# shield-shield.net
KiCad netlist of a schematic drawn in EAGLE
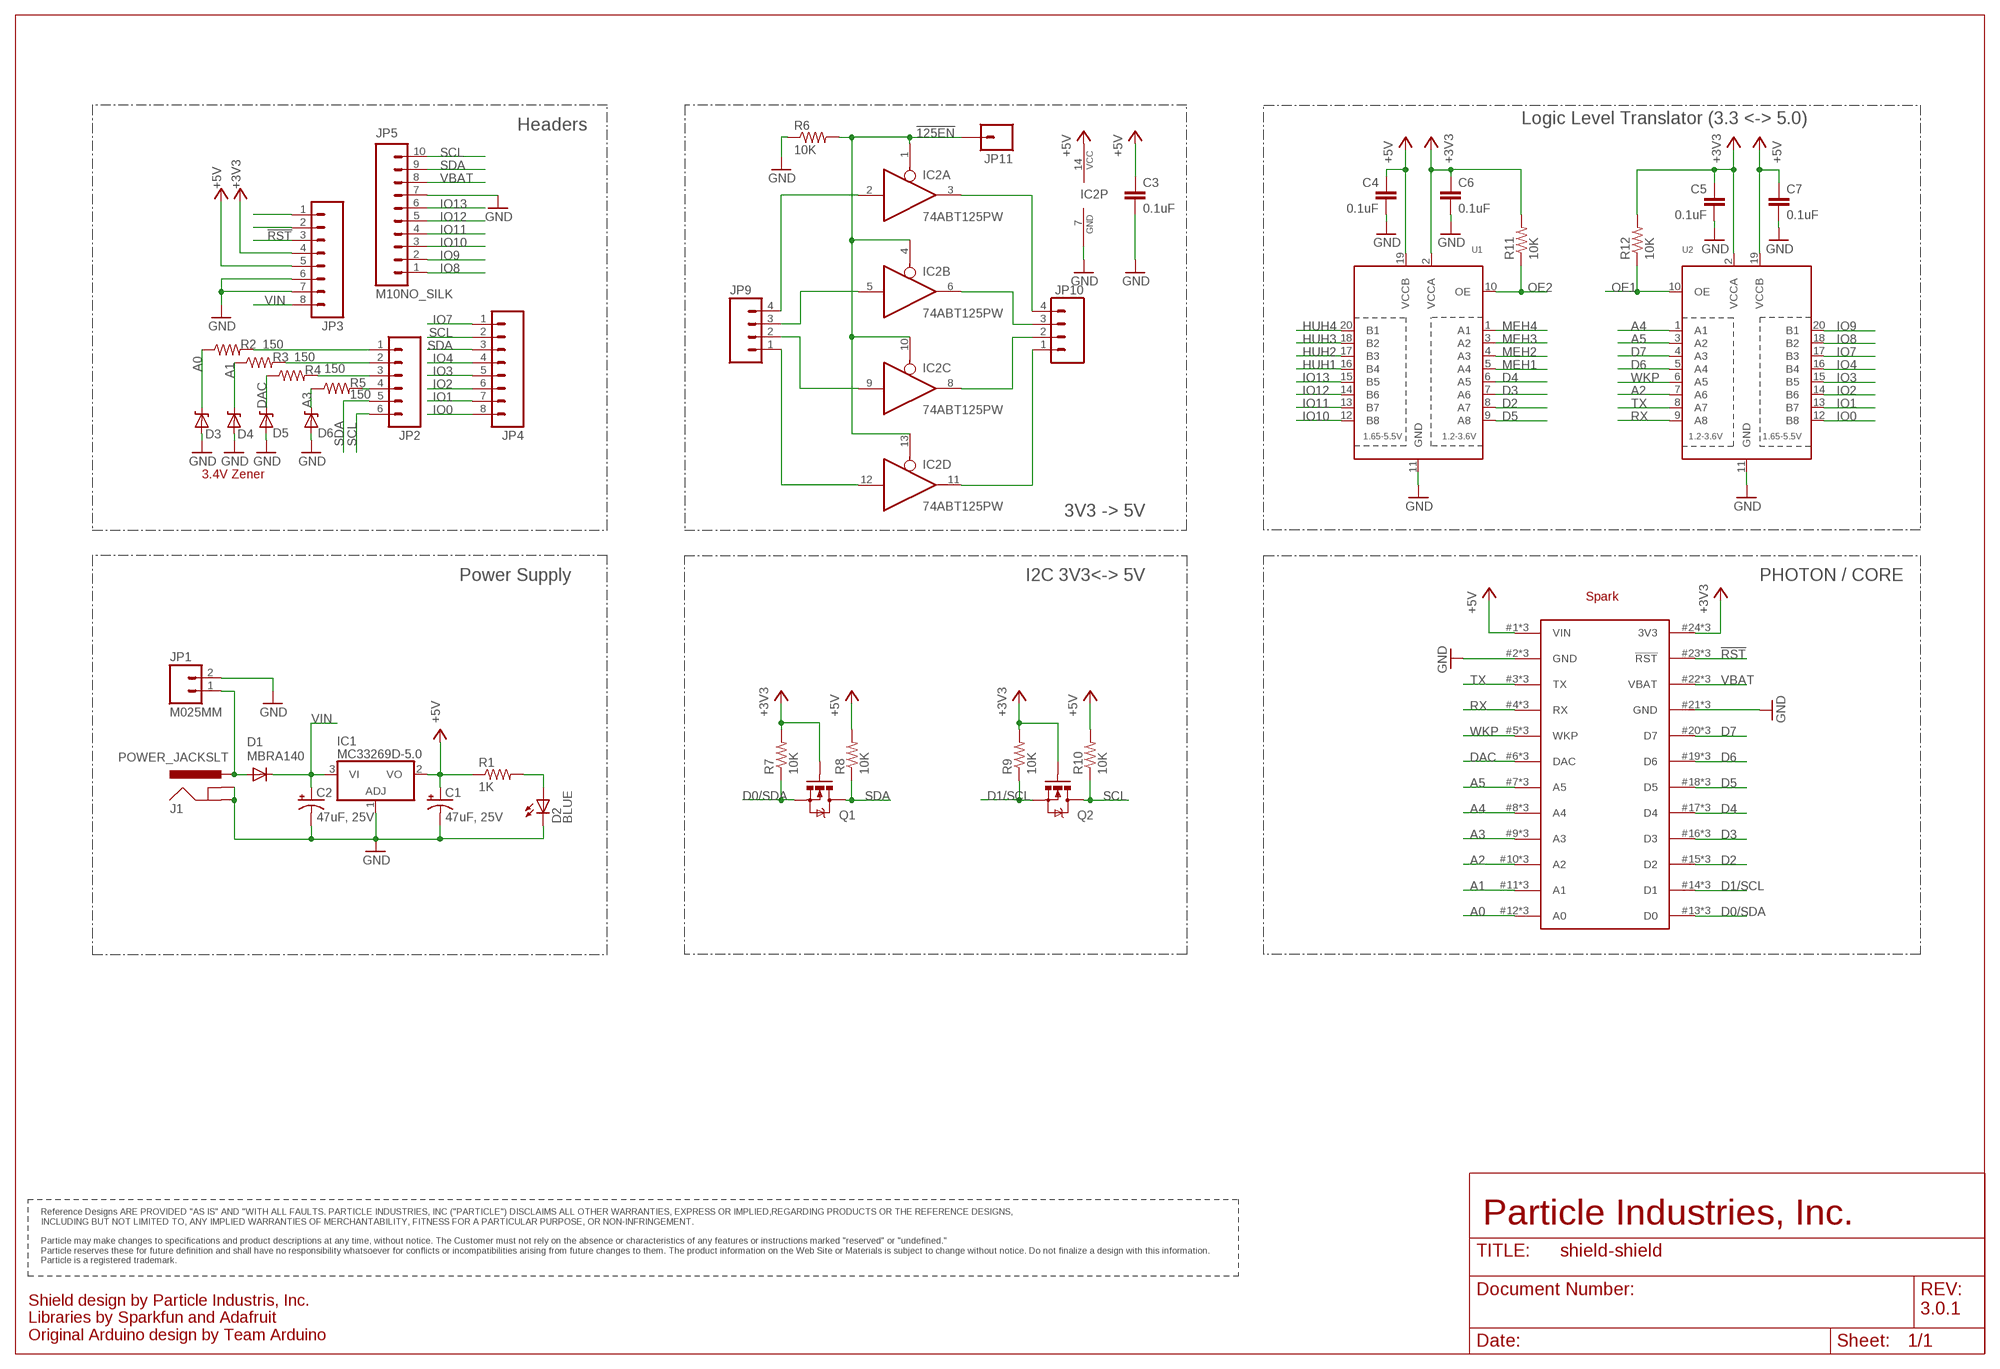
[diagram p0: schematic, sheet 1]

(export (version "E")
  (design (tool "Eeschema 10.0.6"))
  (components
    (comp (ref "C1")
      (value "47uF, 25V")
      (footprint "eagle-import:PANASONIC_D")
      (libsource (lib "eagle-import") (part "CAP_POLD"))
    )
    (comp (ref "C2")
      (value "47uF, 25V")
      (footprint "eagle-import:PANASONIC_D")
      (libsource (lib "eagle-import") (part "CAP_POLD"))
    )
    (comp (ref "C3")
      (value "0.1uF")
      (footprint "eagle-import:0603-CAP")
      (libsource (lib "eagle-import") (part "0.1UF-25V(+80/-20%)(0603)"))
    )
    (comp (ref "C4")
      (value "0.1uF")
      (footprint "eagle-import:0603-CAP")
      (libsource (lib "eagle-import") (part "0.1UF-25V(+80/-20%)(0603)"))
    )
    (comp (ref "C5")
      (value "0.1uF")
      (footprint "eagle-import:0603-CAP")
      (libsource (lib "eagle-import") (part "0.1UF-25V(+80/-20%)(0603)"))
    )
    (comp (ref "C6")
      (value "0.1uF")
      (footprint "eagle-import:0603-CAP")
      (libsource (lib "eagle-import") (part "0.1UF-25V(+80/-20%)(0603)"))
    )
    (comp (ref "C7")
      (value "0.1uF")
      (footprint "eagle-import:0603-CAP")
      (libsource (lib "eagle-import") (part "0.1UF-25V(+80/-20%)(0603)"))
    )
    (comp (ref "D1")
      (value "MBRA140")
      (footprint "eagle-import:SMA-DIODE")
      (libsource (lib "eagle-import") (part "DIODESMA"))
    )
    (comp (ref "D2")
      (value "BLUE")
      (footprint "eagle-import:LED-0603")
      (libsource (lib "eagle-import") (part "LED-BLUE0603"))
    )
    (comp (ref "D3")
      (value "DIODE-ZENER-BZT52")
      (footprint "eagle-import:SOD-323")
      (libsource (lib "eagle-import") (part "DIODE-ZENER-BZT52"))
    )
    (comp (ref "D4")
      (value "DIODE-ZENER-BZT52")
      (footprint "eagle-import:SOD-323")
      (libsource (lib "eagle-import") (part "DIODE-ZENER-BZT52"))
    )
    (comp (ref "D5")
      (value "DIODE-ZENER-BZT52")
      (footprint "eagle-import:SOD-323")
      (libsource (lib "eagle-import") (part "DIODE-ZENER-BZT52"))
    )
    (comp (ref "D6")
      (value "DIODE-ZENER-BZT52")
      (footprint "eagle-import:SOD-323")
      (libsource (lib "eagle-import") (part "DIODE-ZENER-BZT52"))
    )
    (comp (ref "IC1")
      (value "MC33269D-5.0")
      (footprint "eagle-import:DPACK")
      (libsource (lib "eagle-import") (part "MC33269?D-5.0"))
    )
    (comp (ref "IC2")
      (value "74ABT125PW")
      (footprint "eagle-import:TSSOP14")
      (libsource (lib "eagle-import") (part "74125PWABT"))
    )
    (comp (ref "J1")
      (value "POWER_JACKSLT")
      (footprint "eagle-import:POWER_JACK_SLOT")
      (libsource (lib "eagle-import") (part "POWER_JACKSLT"))
    )
    (comp (ref "JP1")
      (value "M025MM")
      (footprint "eagle-import:SCREWTERMINAL-5MM-2")
      (libsource (lib "eagle-import") (part "M025MM"))
    )
    (comp (ref "JP2")
      (value "M06NO_SILK")
      (footprint "eagle-import:1X06_NO_SILK")
      (libsource (lib "eagle-import") (part "M06NO_SILK"))
    )
    (comp (ref "JP3")
      (value "M08NO_SILK")
      (footprint "eagle-import:1X08_NO_SILK")
      (libsource (lib "eagle-import") (part "M08NO_SILK"))
    )
    (comp (ref "JP4")
      (value "M08NO_SILK")
      (footprint "eagle-import:1X08_NO_SILK")
      (libsource (lib "eagle-import") (part "M08NO_SILK"))
    )
    (comp (ref "JP5")
      (value "M10NO_SILK")
      (footprint "eagle-import:1X10_NO_SILK")
      (libsource (lib "eagle-import") (part "M10NO_SILK"))
    )
    (comp (ref "JP9")
      (value "M041X04_NO_SILK")
      (footprint "eagle-import:1X04_NO_SILK")
      (libsource (lib "eagle-import") (part "M041X04_NO_SILK"))
    )
    (comp (ref "JP10")
      (value "M041X04_NO_SILK")
      (footprint "eagle-import:1X04_NO_SILK")
      (libsource (lib "eagle-import") (part "M041X04_NO_SILK"))
    )
    (comp (ref "JP11")
      (value "M01NOSILK-KIT")
      (footprint "eagle-import:1X01NS-KIT")
      (libsource (lib "eagle-import") (part "M01NOSILK-KIT"))
    )
    (comp (ref "Q1")
      (value "MOSFET-NCHANNELBSS138")
      (footprint "eagle-import:SOT23")
      (libsource (lib "eagle-import") (part "MOSFET-NCHANNELBSS138"))
    )
    (comp (ref "Q2")
      (value "MOSFET-NCHANNELBSS138")
      (footprint "eagle-import:SOT23")
      (libsource (lib "eagle-import") (part "MOSFET-NCHANNELBSS138"))
    )
    (comp (ref "R1")
      (value "1K")
      (footprint "eagle-import:0603-RES")
      (libsource (lib "eagle-import") (part "RESISTOR0603-RES"))
    )
    (comp (ref "R2")
      (value "150")
      (footprint "eagle-import:0603-RES")
      (libsource (lib "eagle-import") (part "RESISTOR0603-RES"))
    )
    (comp (ref "R3")
      (value "150")
      (footprint "eagle-import:0603-RES")
      (libsource (lib "eagle-import") (part "RESISTOR0603-RES"))
    )
    (comp (ref "R4")
      (value "150")
      (footprint "eagle-import:0603-RES")
      (libsource (lib "eagle-import") (part "RESISTOR0603-RES"))
    )
    (comp (ref "R5")
      (value "150")
      (footprint "eagle-import:0603-RES")
      (libsource (lib "eagle-import") (part "RESISTOR0603-RES"))
    )
    (comp (ref "R6")
      (value "10K")
      (footprint "eagle-import:0603-RES")
      (libsource (lib "eagle-import") (part "RESISTOR0603-RES"))
    )
    (comp (ref "R7")
      (value "10K")
      (footprint "eagle-import:0603-RES")
      (libsource (lib "eagle-import") (part "RESISTOR0603-RES"))
    )
    (comp (ref "R8")
      (value "10K")
      (footprint "eagle-import:0603-RES")
      (libsource (lib "eagle-import") (part "RESISTOR0603-RES"))
    )
    (comp (ref "R9")
      (value "10K")
      (footprint "eagle-import:0603-RES")
      (libsource (lib "eagle-import") (part "RESISTOR0603-RES"))
    )
    (comp (ref "R10")
      (value "10K")
      (footprint "eagle-import:0603-RES")
      (libsource (lib "eagle-import") (part "RESISTOR0603-RES"))
    )
    (comp (ref "R11")
      (value "10K")
      (footprint "eagle-import:0603-RES")
      (libsource (lib "eagle-import") (part "RESISTOR0603-RES"))
    )
    (comp (ref "R12")
      (value "10K")
      (footprint "eagle-import:0603-RES")
      (libsource (lib "eagle-import") (part "RESISTOR0603-RES"))
    )
    (comp (ref "U$1")
      (value "SPARK_CORE")
      (footprint "eagle-import:SPARK_CORE_STACKABLE")
      (libsource (lib "eagle-import") (part "SPARK_CORESTACKABLE"))
    )
    (comp (ref "U$2")
      (value "SPARK_LOGO")
      (footprint "eagle-import:SPARK_LOGO_TSTOP")
      (libsource (lib "eagle-import") (part "SPARK_LOGO"))
    )
    (comp (ref "U1")
      (value "TXB0108PWR")
      (footprint "eagle-import:TSSOP20")
      (libsource (lib "eagle-import") (part "TXB0108PWR"))
    )
    (comp (ref "U2")
      (value "TXB0108PWR")
      (footprint "eagle-import:TSSOP20")
      (libsource (lib "eagle-import") (part "TXB0108PWR"))
    )
  )
  (nets
    (net (code "1") (name "+3V3") (class "Default")
      (node (ref "C5") (pin "1") (pinfunction "1_1") (pintype "passive"))
      (node (ref "C6") (pin "1") (pinfunction "1_1") (pintype "passive"))
      (node (ref "JP3") (pin "4") (pinfunction "4_4") (pintype "passive"))
      (node (ref "Q1") (pin "1") (pinfunction "G_1") (pintype "passive"))
      (node (ref "Q2") (pin "1") (pinfunction "G_1") (pintype "passive"))
      (node (ref "R11") (pin "2") (pinfunction "2_2") (pintype "passive"))
      (node (ref "R12") (pin "2") (pinfunction "2_2") (pintype "passive"))
      (node (ref "R7") (pin "2") (pinfunction "2_2") (pintype "passive"))
      (node (ref "R9") (pin "2") (pinfunction "2_2") (pintype "passive"))
      (node (ref "U$1") (pin "#24") (pinfunction "3V3_#24") (pintype "power_in"))
      (node (ref "U$1") (pin "24") (pinfunction "3V3_24") (pintype "power_in"))
      (node (ref "U$1") (pin "@24") (pinfunction "3V3_@24") (pintype "power_in"))
      (node (ref "U1") (pin "2") (pinfunction "VCCA_2") (pintype "bidirectional"))
      (node (ref "U2") (pin "2") (pinfunction "VCCA_2") (pintype "bidirectional"))
    )
    (net (code "2") (name "+5V") (class "Default")
      (node (ref "C1") (pin "+") (pinfunction "+_+") (pintype "passive"))
      (node (ref "C3") (pin "1") (pinfunction "1_1") (pintype "passive"))
      (node (ref "C4") (pin "1") (pinfunction "1_1") (pintype "passive"))
      (node (ref "C7") (pin "1") (pinfunction "1_1") (pintype "passive"))
      (node (ref "IC1") (pin "2") (pinfunction "VO_2") (pintype "passive"))
      (node (ref "IC2") (pin "14") (pinfunction "VCC_14") (pintype "power_in"))
      (node (ref "JP3") (pin "5") (pinfunction "5_5") (pintype "passive"))
      (node (ref "R1") (pin "1") (pinfunction "1_1") (pintype "passive"))
      (node (ref "R10") (pin "2") (pinfunction "2_2") (pintype "passive"))
      (node (ref "R8") (pin "2") (pinfunction "2_2") (pintype "passive"))
      (node (ref "U$1") (pin "#1") (pinfunction "VIN_#1") (pintype "power_in"))
      (node (ref "U$1") (pin "1") (pinfunction "VIN_1") (pintype "power_in"))
      (node (ref "U$1") (pin "@1") (pinfunction "VIN_@1") (pintype "power_in"))
      (node (ref "U1") (pin "19") (pinfunction "VCCB_19") (pintype "bidirectional"))
      (node (ref "U2") (pin "19") (pinfunction "VCCB_19") (pintype "bidirectional"))
    )
    (net (code "3") (name "/A0") (class "Default")
      (node (ref "D3") (pin "1") (pinfunction "C_1") (pintype "passive"))
      (node (ref "R2") (pin "1") (pinfunction "1_1") (pintype "passive"))
      (node (ref "U$1") (pin "#12") (pinfunction "A0_#12") (pintype "bidirectional"))
      (node (ref "U$1") (pin "12") (pinfunction "A0_12") (pintype "bidirectional"))
      (node (ref "U$1") (pin "@12") (pinfunction "A0_@12") (pintype "bidirectional"))
    )
    (net (code "4") (name "/A1") (class "Default")
      (node (ref "D4") (pin "1") (pinfunction "C_1") (pintype "passive"))
      (node (ref "R3") (pin "1") (pinfunction "1_1") (pintype "passive"))
      (node (ref "U$1") (pin "#11") (pinfunction "A1_#11") (pintype "bidirectional"))
      (node (ref "U$1") (pin "11") (pinfunction "A1_11") (pintype "bidirectional"))
      (node (ref "U$1") (pin "@11") (pinfunction "A1_@11") (pintype "bidirectional"))
    )
    (net (code "5") (name "/A2") (class "Default")
      (node (ref "U$1") (pin "#10") (pinfunction "A2_#10") (pintype "bidirectional"))
      (node (ref "U$1") (pin "10") (pinfunction "A2_10") (pintype "bidirectional"))
      (node (ref "U$1") (pin "@10") (pinfunction "A2_@10") (pintype "bidirectional"))
      (node (ref "U2") (pin "7") (pinfunction "A6_7") (pintype "bidirectional"))
    )
    (net (code "6") (name "/A3") (class "Default")
      (node (ref "D6") (pin "1") (pinfunction "C_1") (pintype "passive"))
      (node (ref "R5") (pin "1") (pinfunction "1_1") (pintype "passive"))
      (node (ref "U$1") (pin "#9") (pinfunction "A3_#9") (pintype "bidirectional"))
      (node (ref "U$1") (pin "9") (pinfunction "A3_9") (pintype "bidirectional"))
      (node (ref "U$1") (pin "@9") (pinfunction "A3_@9") (pintype "bidirectional"))
    )
    (net (code "7") (name "/A4") (class "Default")
      (node (ref "U$1") (pin "#8") (pinfunction "A4_#8") (pintype "bidirectional"))
      (node (ref "U$1") (pin "8") (pinfunction "A4_8") (pintype "bidirectional"))
      (node (ref "U$1") (pin "@8") (pinfunction "A4_@8") (pintype "bidirectional"))
      (node (ref "U2") (pin "1") (pinfunction "A1_1") (pintype "bidirectional"))
    )
    (net (code "8") (name "/A5") (class "Default")
      (node (ref "U$1") (pin "#7") (pinfunction "A5_#7") (pintype "bidirectional"))
      (node (ref "U$1") (pin "7") (pinfunction "A5_7") (pintype "bidirectional"))
      (node (ref "U$1") (pin "@7") (pinfunction "A5_@7") (pintype "bidirectional"))
      (node (ref "U2") (pin "3") (pinfunction "A2_3") (pintype "bidirectional"))
    )
    (net (code "9") (name "/D0{slash}SDA") (class "Default")
      (node (ref "Q1") (pin "2") (pinfunction "S_2") (pintype "passive"))
      (node (ref "R7") (pin "1") (pinfunction "1_1") (pintype "passive"))
      (node (ref "U$1") (pin "#13") (pinfunction "D0_#13") (pintype "bidirectional"))
      (node (ref "U$1") (pin "13") (pinfunction "D0_13") (pintype "bidirectional"))
      (node (ref "U$1") (pin "@13") (pinfunction "D0_@13") (pintype "bidirectional"))
    )
    (net (code "10") (name "/D1{slash}SCL") (class "Default")
      (node (ref "Q2") (pin "2") (pinfunction "S_2") (pintype "passive"))
      (node (ref "R9") (pin "1") (pinfunction "1_1") (pintype "passive"))
      (node (ref "U$1") (pin "#14") (pinfunction "D1_#14") (pintype "bidirectional"))
      (node (ref "U$1") (pin "14") (pinfunction "D1_14") (pintype "bidirectional"))
      (node (ref "U$1") (pin "@14") (pinfunction "D1_@14") (pintype "bidirectional"))
    )
    (net (code "11") (name "/D2") (class "Default")
      (node (ref "U$1") (pin "#15") (pinfunction "D2_#15") (pintype "bidirectional"))
      (node (ref "U$1") (pin "15") (pinfunction "D2_15") (pintype "bidirectional"))
      (node (ref "U$1") (pin "@15") (pinfunction "D2_@15") (pintype "bidirectional"))
      (node (ref "U1") (pin "8") (pinfunction "A7_8") (pintype "bidirectional"))
    )
    (net (code "12") (name "/D3") (class "Default")
      (node (ref "U$1") (pin "#16") (pinfunction "D3_#16") (pintype "bidirectional"))
      (node (ref "U$1") (pin "16") (pinfunction "D3_16") (pintype "bidirectional"))
      (node (ref "U$1") (pin "@16") (pinfunction "D3_@16") (pintype "bidirectional"))
      (node (ref "U1") (pin "7") (pinfunction "A6_7") (pintype "bidirectional"))
    )
    (net (code "13") (name "/D4") (class "Default")
      (node (ref "U$1") (pin "#17") (pinfunction "D4_#17") (pintype "bidirectional"))
      (node (ref "U$1") (pin "17") (pinfunction "D4_17") (pintype "bidirectional"))
      (node (ref "U$1") (pin "@17") (pinfunction "D4_@17") (pintype "bidirectional"))
      (node (ref "U1") (pin "6") (pinfunction "A5_6") (pintype "bidirectional"))
    )
    (net (code "14") (name "/D5") (class "Default")
      (node (ref "U$1") (pin "#18") (pinfunction "D5_#18") (pintype "bidirectional"))
      (node (ref "U$1") (pin "18") (pinfunction "D5_18") (pintype "bidirectional"))
      (node (ref "U$1") (pin "@18") (pinfunction "D5_@18") (pintype "bidirectional"))
      (node (ref "U1") (pin "9") (pinfunction "A8_9") (pintype "bidirectional"))
    )
    (net (code "15") (name "/D6") (class "Default")
      (node (ref "U$1") (pin "#19") (pinfunction "D6_#19") (pintype "bidirectional"))
      (node (ref "U$1") (pin "19") (pinfunction "D6_19") (pintype "bidirectional"))
      (node (ref "U$1") (pin "@19") (pinfunction "D6_@19") (pintype "bidirectional"))
      (node (ref "U2") (pin "5") (pinfunction "A4_5") (pintype "bidirectional"))
    )
    (net (code "16") (name "/D7") (class "Default")
      (node (ref "U$1") (pin "#20") (pinfunction "D7_#20") (pintype "bidirectional"))
      (node (ref "U$1") (pin "20") (pinfunction "D7_20") (pintype "bidirectional"))
      (node (ref "U$1") (pin "@20") (pinfunction "D7_@20") (pintype "bidirectional"))
      (node (ref "U2") (pin "4") (pinfunction "A3_4") (pintype "bidirectional"))
    )
    (net (code "17") (name "/DAC") (class "Default")
      (node (ref "D5") (pin "1") (pinfunction "C_1") (pintype "passive"))
      (node (ref "R4") (pin "1") (pinfunction "1_1") (pintype "passive"))
      (node (ref "U$1") (pin "#6") (pinfunction "DAC_#6") (pintype "bidirectional"))
      (node (ref "U$1") (pin "6") (pinfunction "DAC_6") (pintype "bidirectional"))
      (node (ref "U$1") (pin "@6") (pinfunction "DAC_@6") (pintype "bidirectional"))
    )
    (net (code "18") (name "/HUH1") (class "Default")
      (node (ref "U1") (pin "16") (pinfunction "B4_16") (pintype "bidirectional"))
    )
    (net (code "19") (name "/HUH2") (class "Default")
      (node (ref "U1") (pin "17") (pinfunction "B3_17") (pintype "bidirectional"))
    )
    (net (code "20") (name "/HUH3") (class "Default")
      (node (ref "U1") (pin "18") (pinfunction "B2_18") (pintype "bidirectional"))
    )
    (net (code "21") (name "/HUH4") (class "Default")
      (node (ref "U1") (pin "20") (pinfunction "B1_20") (pintype "bidirectional"))
    )
    (net (code "22") (name "/IO0") (class "Default")
      (node (ref "JP4") (pin "8") (pinfunction "8_8") (pintype "passive"))
      (node (ref "U2") (pin "12") (pinfunction "B8_12") (pintype "bidirectional"))
    )
    (net (code "23") (name "/IO1") (class "Default")
      (node (ref "JP4") (pin "7") (pinfunction "7_7") (pintype "passive"))
      (node (ref "U2") (pin "13") (pinfunction "B7_13") (pintype "bidirectional"))
    )
    (net (code "24") (name "/IO2") (class "Default")
      (node (ref "JP4") (pin "6") (pinfunction "6_6") (pintype "passive"))
      (node (ref "U2") (pin "14") (pinfunction "B6_14") (pintype "bidirectional"))
    )
    (net (code "25") (name "/IO3") (class "Default")
      (node (ref "JP4") (pin "5") (pinfunction "5_5") (pintype "passive"))
      (node (ref "U2") (pin "15") (pinfunction "B5_15") (pintype "bidirectional"))
    )
    (net (code "26") (name "/IO4") (class "Default")
      (node (ref "JP4") (pin "4") (pinfunction "4_4") (pintype "passive"))
      (node (ref "U2") (pin "16") (pinfunction "B4_16") (pintype "bidirectional"))
    )
    (net (code "27") (name "/IO7") (class "Default")
      (node (ref "JP4") (pin "1") (pinfunction "1_1") (pintype "passive"))
      (node (ref "U2") (pin "17") (pinfunction "B3_17") (pintype "bidirectional"))
    )
    (net (code "28") (name "/IO8") (class "Default")
      (node (ref "JP5") (pin "1") (pinfunction "1_1") (pintype "passive"))
      (node (ref "U2") (pin "18") (pinfunction "B2_18") (pintype "bidirectional"))
    )
    (net (code "29") (name "/IO9") (class "Default")
      (node (ref "JP5") (pin "2") (pinfunction "2_2") (pintype "passive"))
      (node (ref "U2") (pin "20") (pinfunction "B1_20") (pintype "bidirectional"))
    )
    (net (code "30") (name "/IO10") (class "Default")
      (node (ref "JP5") (pin "3") (pinfunction "3_3") (pintype "passive"))
      (node (ref "U1") (pin "12") (pinfunction "B8_12") (pintype "bidirectional"))
    )
    (net (code "31") (name "/IO11") (class "Default")
      (node (ref "JP5") (pin "4") (pinfunction "4_4") (pintype "passive"))
      (node (ref "U1") (pin "13") (pinfunction "B7_13") (pintype "bidirectional"))
    )
    (net (code "32") (name "/IO12") (class "Default")
      (node (ref "JP5") (pin "5") (pinfunction "5_5") (pintype "passive"))
      (node (ref "U1") (pin "14") (pinfunction "B6_14") (pintype "bidirectional"))
    )
    (net (code "33") (name "/IO13") (class "Default")
      (node (ref "JP5") (pin "6") (pinfunction "6_6") (pintype "passive"))
      (node (ref "U1") (pin "15") (pinfunction "B5_15") (pintype "bidirectional"))
    )
    (net (code "34") (name "/MEH1") (class "Default")
      (node (ref "U1") (pin "5") (pinfunction "A4_5") (pintype "bidirectional"))
    )
    (net (code "35") (name "/MEH2") (class "Default")
      (node (ref "U1") (pin "4") (pinfunction "A3_4") (pintype "bidirectional"))
    )
    (net (code "36") (name "/MEH3") (class "Default")
      (node (ref "U1") (pin "3") (pinfunction "A2_3") (pintype "bidirectional"))
    )
    (net (code "37") (name "/MEH4") (class "Default")
      (node (ref "U1") (pin "1") (pinfunction "A1_1") (pintype "bidirectional"))
    )
    (net (code "38") (name "/OE1") (class "Default")
      (node (ref "R12") (pin "1") (pinfunction "1_1") (pintype "passive"))
      (node (ref "U2") (pin "10") (pinfunction "OE_10") (pintype "bidirectional"))
    )
    (net (code "39") (name "/OE2") (class "Default")
      (node (ref "R11") (pin "1") (pinfunction "1_1") (pintype "passive"))
      (node (ref "U1") (pin "10") (pinfunction "OE_10") (pintype "bidirectional"))
    )
    (net (code "40") (name "/RX") (class "Default")
      (node (ref "U$1") (pin "#4") (pinfunction "RX_#4") (pintype "bidirectional"))
      (node (ref "U$1") (pin "4") (pinfunction "RX_4") (pintype "bidirectional"))
      (node (ref "U$1") (pin "@4") (pinfunction "RX_@4") (pintype "bidirectional"))
      (node (ref "U2") (pin "9") (pinfunction "A8_9") (pintype "bidirectional"))
    )
    (net (code "41") (name "/SCL") (class "Default")
      (node (ref "JP2") (pin "6") (pinfunction "6_6") (pintype "passive"))
      (node (ref "JP4") (pin "2") (pinfunction "2_2") (pintype "passive"))
      (node (ref "JP5") (pin "10") (pinfunction "10_10") (pintype "passive"))
      (node (ref "Q2") (pin "3") (pinfunction "D_3") (pintype "passive"))
      (node (ref "R10") (pin "1") (pinfunction "1_1") (pintype "passive"))
    )
    (net (code "42") (name "/SDA") (class "Default")
      (node (ref "JP2") (pin "5") (pinfunction "5_5") (pintype "passive"))
      (node (ref "JP4") (pin "3") (pinfunction "3_3") (pintype "passive"))
      (node (ref "JP5") (pin "9") (pinfunction "9_9") (pintype "passive"))
      (node (ref "Q1") (pin "3") (pinfunction "D_3") (pintype "passive"))
      (node (ref "R8") (pin "1") (pinfunction "1_1") (pintype "passive"))
    )
    (net (code "43") (name "/TX") (class "Default")
      (node (ref "U$1") (pin "#3") (pinfunction "TX_#3") (pintype "bidirectional"))
      (node (ref "U$1") (pin "3") (pinfunction "TX_3") (pintype "bidirectional"))
      (node (ref "U$1") (pin "@3") (pinfunction "TX_@3") (pintype "bidirectional"))
      (node (ref "U2") (pin "8") (pinfunction "A7_8") (pintype "bidirectional"))
    )
    (net (code "44") (name "/VBAT") (class "Default")
      (node (ref "JP5") (pin "8") (pinfunction "8_8") (pintype "passive"))
      (node (ref "U$1") (pin "#22") (pinfunction "VBAT_#22") (pintype "power_in"))
      (node (ref "U$1") (pin "22") (pinfunction "VBAT_22") (pintype "power_in"))
      (node (ref "U$1") (pin "@22") (pinfunction "VBAT_@22") (pintype "power_in"))
    )
    (net (code "45") (name "/VIN") (class "Default")
      (node (ref "C2") (pin "+") (pinfunction "+_+") (pintype "passive"))
      (node (ref "D1") (pin "C") (pinfunction "C_C") (pintype "passive"))
      (node (ref "IC1") (pin "3") (pinfunction "VI_3") (pintype "input"))
      (node (ref "JP3") (pin "8") (pinfunction "8_8") (pintype "passive"))
    )
    (net (code "46") (name "/WKP") (class "Default")
      (node (ref "U$1") (pin "#5") (pinfunction "WKP_#5") (pintype "bidirectional"))
      (node (ref "U$1") (pin "5") (pinfunction "WKP_5") (pintype "bidirectional"))
      (node (ref "U$1") (pin "@5") (pinfunction "WKP_@5") (pintype "bidirectional"))
      (node (ref "U2") (pin "6") (pinfunction "A5_6") (pintype "bidirectional"))
    )
    (net (code "47") (name "/~{125EN}") (class "Default")
      (node (ref "IC2") (pin "1") (pinfunction "OE_1") (pintype "input"))
      (node (ref "IC2") (pin "10") (pinfunction "OE_10") (pintype "input"))
      (node (ref "IC2") (pin "13") (pinfunction "OE_13") (pintype "input"))
      (node (ref "IC2") (pin "4") (pinfunction "OE_4") (pintype "input"))
      (node (ref "JP11") (pin "1") (pinfunction "1_1") (pintype "passive"))
      (node (ref "R6") (pin "2") (pinfunction "2_2") (pintype "passive"))
    )
    (net (code "48") (name "/~{RST}") (class "Default")
      (node (ref "JP3") (pin "3") (pinfunction "3_3") (pintype "passive"))
      (node (ref "U$1") (pin "#23") (pinfunction "~{RST}_#23") (pintype "bidirectional"))
      (node (ref "U$1") (pin "23") (pinfunction "~{RST}_23") (pintype "bidirectional"))
      (node (ref "U$1") (pin "@23") (pinfunction "~{RST}_@23") (pintype "bidirectional"))
    )
    (net (code "49") (name "GND") (class "Default")
      (node (ref "C1") (pin "-") (pinfunction "-_-") (pintype "passive"))
      (node (ref "C2") (pin "-") (pinfunction "-_-") (pintype "passive"))
      (node (ref "C3") (pin "2") (pinfunction "2_2") (pintype "passive"))
      (node (ref "C4") (pin "2") (pinfunction "2_2") (pintype "passive"))
      (node (ref "C5") (pin "2") (pinfunction "2_2") (pintype "passive"))
      (node (ref "C6") (pin "2") (pinfunction "2_2") (pintype "passive"))
      (node (ref "C7") (pin "2") (pinfunction "2_2") (pintype "passive"))
      (node (ref "D2") (pin "C") (pinfunction "C_C") (pintype "passive"))
      (node (ref "D3") (pin "2") (pinfunction "A_2") (pintype "passive"))
      (node (ref "D4") (pin "2") (pinfunction "A_2") (pintype "passive"))
      (node (ref "D5") (pin "2") (pinfunction "A_2") (pintype "passive"))
      (node (ref "D6") (pin "2") (pinfunction "A_2") (pintype "passive"))
      (node (ref "IC1") (pin "1") (pinfunction "ADJ_1") (pintype "input"))
      (node (ref "IC2") (pin "7") (pinfunction "GND_7") (pintype "power_in"))
      (node (ref "J1") (pin "GND@1") (pinfunction "GNDBREAK_GND@1") (pintype "bidirectional"))
      (node (ref "J1") (pin "GND@2") (pinfunction "GND_GND@2") (pintype "bidirectional"))
      (node (ref "JP1") (pin "2") (pinfunction "2_2") (pintype "passive"))
      (node (ref "JP3") (pin "6") (pinfunction "6_6") (pintype "passive"))
      (node (ref "JP3") (pin "7") (pinfunction "7_7") (pintype "passive"))
      (node (ref "JP5") (pin "7") (pinfunction "7_7") (pintype "passive"))
      (node (ref "R6") (pin "1") (pinfunction "1_1") (pintype "passive"))
      (node (ref "U$1") (pin "#2") (pinfunction "GND_#2") (pintype "power_in"))
      (node (ref "U$1") (pin "#21") (pinfunction "GND_#21") (pintype "power_in"))
      (node (ref "U$1") (pin "2") (pinfunction "GND_2") (pintype "power_in"))
      (node (ref "U$1") (pin "21") (pinfunction "GND_21") (pintype "power_in"))
      (node (ref "U$1") (pin "@2") (pinfunction "GND_@2") (pintype "power_in"))
      (node (ref "U$1") (pin "@21") (pinfunction "GND_@21") (pintype "power_in"))
      (node (ref "U1") (pin "11") (pinfunction "GND_11") (pintype "bidirectional"))
      (node (ref "U2") (pin "11") (pinfunction "GND_11") (pintype "bidirectional"))
    )
    (net (code "50") (name "Net-(D1-PadA)") (class "Default")
      (node (ref "D1") (pin "A") (pinfunction "A_A") (pintype "passive"))
      (node (ref "J1") (pin "PWR") (pinfunction "PWR_PWR") (pintype "bidirectional"))
      (node (ref "JP1") (pin "1") (pinfunction "1_1") (pintype "passive"))
    )
    (net (code "51") (name "Net-(D2-PadA)") (class "Default")
      (node (ref "D2") (pin "A") (pinfunction "A_A") (pintype "passive"))
      (node (ref "R1") (pin "2") (pinfunction "2_2") (pintype "passive"))
    )
    (net (code "52") (name "Net-(IC2A-I)") (class "Default")
      (node (ref "IC2") (pin "2") (pinfunction "I_2") (pintype "input"))
      (node (ref "JP9") (pin "4") (pinfunction "4_4") (pintype "passive"))
    )
    (net (code "53") (name "Net-(IC2A-O)") (class "Default")
      (node (ref "IC2") (pin "3") (pinfunction "O_3") (pintype "tri_state"))
      (node (ref "JP10") (pin "4") (pinfunction "4_4") (pintype "passive"))
    )
    (net (code "54") (name "Net-(IC2B-I)") (class "Default")
      (node (ref "IC2") (pin "5") (pinfunction "I_5") (pintype "input"))
      (node (ref "JP9") (pin "3") (pinfunction "3_3") (pintype "passive"))
    )
    (net (code "55") (name "Net-(IC2B-O)") (class "Default")
      (node (ref "IC2") (pin "6") (pinfunction "O_6") (pintype "tri_state"))
      (node (ref "JP10") (pin "3") (pinfunction "3_3") (pintype "passive"))
    )
    (net (code "56") (name "Net-(IC2C-I)") (class "Default")
      (node (ref "IC2") (pin "9") (pinfunction "I_9") (pintype "input"))
      (node (ref "JP9") (pin "2") (pinfunction "2_2") (pintype "passive"))
    )
    (net (code "57") (name "Net-(IC2C-O)") (class "Default")
      (node (ref "IC2") (pin "8") (pinfunction "O_8") (pintype "tri_state"))
      (node (ref "JP10") (pin "2") (pinfunction "2_2") (pintype "passive"))
    )
    (net (code "58") (name "Net-(IC2D-I)") (class "Default")
      (node (ref "IC2") (pin "12") (pinfunction "I_12") (pintype "input"))
      (node (ref "JP9") (pin "1") (pinfunction "1_1") (pintype "passive"))
    )
    (net (code "59") (name "Net-(IC2D-O)") (class "Default")
      (node (ref "IC2") (pin "11") (pinfunction "O_11") (pintype "tri_state"))
      (node (ref "JP10") (pin "1") (pinfunction "1_1") (pintype "passive"))
    )
    (net (code "60") (name "Net-(JP2-Pad1)") (class "Default")
      (node (ref "JP2") (pin "1") (pinfunction "1_1") (pintype "passive"))
      (node (ref "R2") (pin "2") (pinfunction "2_2") (pintype "passive"))
    )
    (net (code "61") (name "Net-(JP2-Pad2)") (class "Default")
      (node (ref "JP2") (pin "2") (pinfunction "2_2") (pintype "passive"))
      (node (ref "R3") (pin "2") (pinfunction "2_2") (pintype "passive"))
    )
    (net (code "62") (name "Net-(JP2-Pad3)") (class "Default")
      (node (ref "JP2") (pin "3") (pinfunction "3_3") (pintype "passive"))
      (node (ref "R4") (pin "2") (pinfunction "2_2") (pintype "passive"))
    )
    (net (code "63") (name "Net-(JP2-Pad4)") (class "Default")
      (node (ref "JP2") (pin "4") (pinfunction "4_4") (pintype "passive"))
      (node (ref "R5") (pin "2") (pinfunction "2_2") (pintype "passive"))
    )
    (net (code "64") (name "unconnected-(JP3-Pad1)") (class "Default")
      (node (ref "JP3") (pin "1") (pinfunction "1_1") (pintype "passive"))
    )
    (net (code "65") (name "unconnected-(JP3-Pad2)") (class "Default")
      (node (ref "JP3") (pin "2") (pinfunction "2_2") (pintype "passive"))
    )
  )
)
